# thermistor-vacuum-sensor.net
KiCad netlist of a schematic drawn in EAGLE
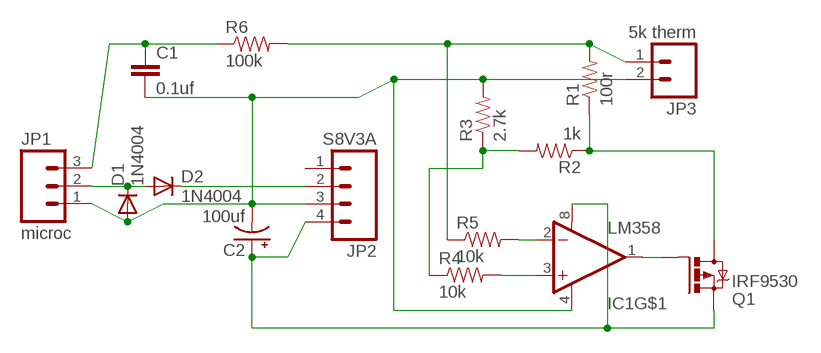
[diagram p0: schematic, sheet 1]

(export (version "E")
  (design (tool "Eeschema 10.0.6"))
  (components
    (comp (ref "C1")
      (value "0.1uf")
      (footprint "eagle-import:CAP-PTH-SMALL")
      (libsource (lib "eagle-import") (part "CAPPTH"))
    )
    (comp (ref "C2")
      (value "100uf")
      (footprint "eagle-import:CPOL-RADIAL-100UF-25V")
      (libsource (lib "eagle-import") (part "CAP_POLPTH1"))
    )
    (comp (ref "D1")
      (value "1N4004")
      (footprint "eagle-import:DO41-10")
      (libsource (lib "eagle-import") (part "1N4004"))
    )
    (comp (ref "D2")
      (value "1N4004")
      (footprint "eagle-import:DO41-10")
      (libsource (lib "eagle-import") (part "1N4004"))
    )
    (comp (ref "IC1")
      (value "LM358")
      (footprint "eagle-import:DIP08")
      (libsource (lib "eagle-import") (part "LM358"))
    )
    (comp (ref "JP1")
      (value "microc")
      (footprint "eagle-import:1X03_LONGPADS")
      (libsource (lib "eagle-import") (part "M03LONGPADS"))
    )
    (comp (ref "JP2")
      (value "S8V3A")
      (footprint "eagle-import:1X04_LONGPADS")
      (libsource (lib "eagle-import") (part "M04LONGPADS"))
    )
    (comp (ref "JP3")
      (value "5k therm")
      (footprint "eagle-import:1X02_LOCK_LONGPADS")
      (libsource (lib "eagle-import") (part "M02LOCK_LONGPADS"))
    )
    (comp (ref "Q1")
      (value "IRF9530")
      (footprint "eagle-import:TO220BV")
      (libsource (lib "eagle-import") (part "IRF9530"))
    )
    (comp (ref "R1")
      (value "100r")
      (footprint "eagle-import:AXIAL-0.3")
      (libsource (lib "eagle-import") (part "RESISTORAXIAL-0.3-FRANK"))
    )
    (comp (ref "R2")
      (value "1k")
      (footprint "eagle-import:AXIAL-0.3")
      (libsource (lib "eagle-import") (part "RESISTORAXIAL-0.3-FRANK"))
    )
    (comp (ref "R3")
      (value "2.7k")
      (footprint "eagle-import:AXIAL-0.3")
      (libsource (lib "eagle-import") (part "RESISTORAXIAL-0.3-FRANK"))
    )
    (comp (ref "R4")
      (value "10k")
      (footprint "eagle-import:AXIAL-0.3")
      (libsource (lib "eagle-import") (part "RESISTORAXIAL-0.3-FRANK"))
    )
    (comp (ref "R5")
      (value "10k")
      (footprint "eagle-import:AXIAL-0.3")
      (libsource (lib "eagle-import") (part "RESISTORAXIAL-0.3-FRANK"))
    )
    (comp (ref "R6")
      (value "100k")
      (footprint "eagle-import:AXIAL-0.3")
      (libsource (lib "eagle-import") (part "RESISTORAXIAL-0.3-FRANK"))
    )
  )
  (nets
    (net (code "1") (name "Net-(C2-+)") (class "Default")
      (node (ref "C2") (pin "1") (pinfunction "+_1") (pintype "passive"))
      (node (ref "IC1") (pin "8") (pinfunction "V+_8") (pintype "power_in"))
      (node (ref "JP2") (pin "4") (pinfunction "4_4") (pintype "passive"))
      (node (ref "Q1") (pin "S") (pinfunction "S_S") (pintype "passive"))
    )
    (net (code "2") (name "Net-(C2--)") (class "Default")
      (node (ref "C1") (pin "2") (pinfunction "2_2") (pintype "passive"))
      (node (ref "C2") (pin "2") (pinfunction "-_2") (pintype "passive"))
      (node (ref "D1") (pin "A") (pinfunction "A_A") (pintype "passive"))
      (node (ref "IC1") (pin "4") (pinfunction "V-_4") (pintype "power_in"))
      (node (ref "JP1") (pin "1") (pinfunction "1_1") (pintype "passive"))
      (node (ref "JP2") (pin "3") (pinfunction "3_3") (pintype "passive"))
      (node (ref "JP3") (pin "2") (pinfunction "2_2") (pintype "passive"))
      (node (ref "R3") (pin "P$2") (pinfunction "2_P$2") (pintype "passive"))
    )
    (net (code "3") (name "Net-(D1-PadC)") (class "Default")
      (node (ref "D1") (pin "C") (pinfunction "C_C") (pintype "passive"))
      (node (ref "D2") (pin "A") (pinfunction "A_A") (pintype "passive"))
      (node (ref "JP1") (pin "2") (pinfunction "2_2") (pintype "passive"))
    )
    (net (code "4") (name "Net-(D2-PadC)") (class "Default")
      (node (ref "D2") (pin "C") (pinfunction "C_C") (pintype "passive"))
      (node (ref "JP2") (pin "2") (pinfunction "2_2") (pintype "passive"))
    )
    (net (code "5") (name "Net-(IC1A-+IN)") (class "Default")
      (node (ref "IC1") (pin "3") (pinfunction "+IN_3") (pintype "input"))
      (node (ref "R4") (pin "P$2") (pinfunction "2_P$2") (pintype "passive"))
    )
    (net (code "6") (name "Net-(IC1A--IN)") (class "Default")
      (node (ref "IC1") (pin "2") (pinfunction "-IN_2") (pintype "input"))
      (node (ref "R5") (pin "P$2") (pinfunction "2_P$2") (pintype "passive"))
    )
    (net (code "7") (name "Net-(IC1A-OUT)") (class "Default")
      (node (ref "IC1") (pin "1") (pinfunction "OUT_1") (pintype "output"))
      (node (ref "Q1") (pin "G") (pinfunction "G_G") (pintype "passive"))
    )
    (net (code "8") (name "Net-(R1-1)") (class "Default")
      (node (ref "Q1") (pin "D") (pinfunction "D_D") (pintype "passive"))
      (node (ref "R1") (pin "P$1") (pinfunction "1_P$1") (pintype "passive"))
      (node (ref "R2") (pin "P$1") (pinfunction "1_P$1") (pintype "passive"))
    )
    (net (code "9") (name "Net-(R1-2)") (class "Default")
      (node (ref "JP3") (pin "1") (pinfunction "1_1") (pintype "passive"))
      (node (ref "R1") (pin "P$2") (pinfunction "2_P$2") (pintype "passive"))
      (node (ref "R5") (pin "P$1") (pinfunction "1_P$1") (pintype "passive"))
      (node (ref "R6") (pin "P$2") (pinfunction "2_P$2") (pintype "passive"))
    )
    (net (code "10") (name "Net-(R2-2)") (class "Default")
      (node (ref "R2") (pin "P$2") (pinfunction "2_P$2") (pintype "passive"))
      (node (ref "R3") (pin "P$1") (pinfunction "1_P$1") (pintype "passive"))
      (node (ref "R4") (pin "P$1") (pinfunction "1_P$1") (pintype "passive"))
    )
    (net (code "11") (name "Net-(R6-1)") (class "Default")
      (node (ref "C1") (pin "1") (pinfunction "1_1") (pintype "passive"))
      (node (ref "JP1") (pin "3") (pinfunction "3_3") (pintype "passive"))
      (node (ref "R6") (pin "P$1") (pinfunction "1_P$1") (pintype "passive"))
    )
    (net (code "12") (name "unconnected-(JP2-Pad1)") (class "Default")
      (node (ref "JP2") (pin "1") (pinfunction "1_1") (pintype "passive"))
    )
  )
)
